# PWR.net
KiCad netlist of a schematic drawn in Altium Designer
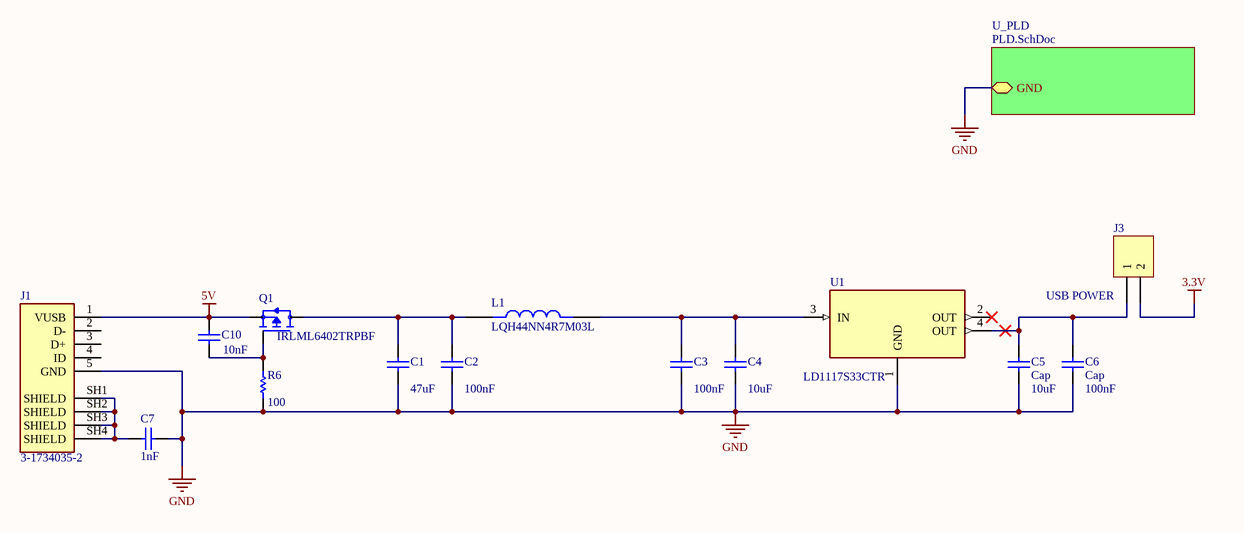
[diagram p0: PWR.SchDoc]

(export (version "E")
  (design (tool "Eeschema 10.0.6"))
  (components
    (comp (ref "C1")
      (value "47uF")
      (footprint "WCAP-CSGP_885012209019")
      (description "Capacitor")
      (fields (field (name "Comment") "Cap") (field (name "PUBLISHER") "Altium Limited"))
      (libsource (lib "Miscellaneous Devices") (part "Cap"))
    )
    (comp (ref "C2")
      (value "100nF")
      (footprint "WCAP-CSST_885382207009")
      (description "Capacitor")
      (fields (field (name "Comment") "Cap") (field (name "PUBLISHER") "Altium Limited"))
      (libsource (lib "Miscellaneous Devices") (part "Cap"))
    )
    (comp (ref "C3")
      (value "100nF")
      (footprint "WCAP-CSST_885382207009")
      (description "Capacitor")
      (fields (field (name "Comment") "Cap") (field (name "PUBLISHER") "Altium Limited"))
      (libsource (lib "Miscellaneous Devices") (part "Cap"))
    )
    (comp (ref "C4")
      (value "10uF")
      (footprint "WCAP-CSST_885382207009")
      (description "Capacitor")
      (fields (field (name "Comment") "Cap") (field (name "PUBLISHER") "Altium Limited"))
      (libsource (lib "Miscellaneous Devices") (part "Cap"))
    )
    (comp (ref "C5")
      (value "Cap")
      (footprint "WCAP-CSST_885382207009")
      (description "Capacitor")
      (fields (field (name "ALTIUM_VALUE") "10uF") (field (name "PUBLISHER") "Altium Limited"))
      (libsource (lib "Miscellaneous Devices") (part "Cap"))
    )
    (comp (ref "C6")
      (value "Cap")
      (footprint "WCAP-CSST_885382207009")
      (description "Capacitor")
      (fields (field (name "ALTIUM_VALUE") "100nF") (field (name "PUBLISHER") "Altium Limited"))
      (libsource (lib "Miscellaneous Devices") (part "Cap"))
    )
    (comp (ref "C7")
      (value "1nF")
      (footprint "WCAP-CSST_885382207009")
      (description "Capacitor")
      (fields (field (name "Comment") "Cap") (field (name "PUBLISHER") "Altium Limited"))
      (libsource (lib "Miscellaneous Devices") (part "Cap"))
    )
    (comp (ref "C10")
      (value "10nF")
      (footprint "WCAP-CSST_885382207009")
      (description "Capacitor")
      (fields (field (name "Comment") "Cap") (field (name "PUBLISHER") "Altium Limited"))
      (libsource (lib "Miscellaneous Devices") (part "Cap"))
    )
    (comp (ref "J1")
      (value "3-1734035-2")
      (footprint "TE_3-1734035-2")
      (description "USB Connectors MINI USB, R/A, SMT, MATTE TIN, W/O MYLAR")
      (fields (field (name "MF") "TE Connectivity"))
      (libsource (lib "3-1734035-2") (part "3-1734035-2"))
    )
    (comp (ref "J3")
      (value "USB POWER")
      (footprint "HDR1X2")
      (description "Header, 2-Pin")
      (fields (field (name "PUBLISHER") "Altium Limited"))
      (libsource (lib "Miscellaneous Connectors") (part "Header 2"))
    )
    (comp (ref "L1")
      (value "LQH44NN4R7M03L")
      (footprint "IND_LQH44NN4R7M03L")
      (description "FIXED IND 22UH 950MA 170 MOHM")
      (libsource (lib "LQH44NN4R7M03L") (part "LQH44NN4R7M03L"))
    )
    (comp (ref "Q1")
      (value "IRLML6402TRPBF")
      (footprint "SOT95P237X112-3N")
      (fields (field (name "MF") "Infineon"))
      (libsource (lib "IRLML6402TRPBF") (part "IRLML6402TRPBF"))
    )
    (comp (ref "R6")
      (value "100")
      (footprint "WCAP-CSST_885382207009")
      (description "Resistor")
      (fields (field (name "Comment") "Res1") (field (name "PUBLISHER") "Altium Limited"))
      (libsource (lib "Miscellaneous Devices") (part "Res1"))
    )
    (comp (ref "U1")
      (value "LD1117S33CTR")
      (footprint "SOT223")
      (description "Linear Voltage Regulator IC Positive Fixed 1 Output 800mA SOT-223")
      (fields (field (name "MF") "STMicroelectronics"))
      (libsource (lib "LD1117S33CTR") (part "LD1117S33CTR"))
    )
  )
  (nets
    (net (code "1") (name "3.3V") (class "Default")
      (node (ref "J3") (pin "2") (pinfunction "2_2") (pintype "passive"))
    )
    (net (code "2") (name "5V") (class "Default")
      (node (ref "C10") (pin "2") (pinfunction "2_2") (pintype "passive"))
      (node (ref "J1") (pin "1") (pinfunction "VUSB_1") (pintype "passive"))
      (node (ref "Q1") (pin "2") (pinfunction "S_2") (pintype "passive"))
    )
    (net (code "3") (name "GND") (class "Default")
      (node (ref "C1") (pin "1") (pinfunction "1_1") (pintype "passive"))
      (node (ref "C2") (pin "1") (pinfunction "1_1") (pintype "passive"))
      (node (ref "C3") (pin "1") (pinfunction "1_1") (pintype "passive"))
      (node (ref "C4") (pin "1") (pinfunction "1_1") (pintype "passive"))
      (node (ref "C5") (pin "1") (pinfunction "1_1") (pintype "passive"))
      (node (ref "C6") (pin "1") (pinfunction "1_1") (pintype "passive"))
      (node (ref "C7") (pin "2") (pinfunction "2_2") (pintype "passive"))
      (node (ref "J1") (pin "5") (pinfunction "GND_5") (pintype "passive"))
      (node (ref "R6") (pin "1") (pinfunction "1_1") (pintype "passive"))
      (node (ref "U1") (pin "1") (pinfunction "GND_1") (pintype "passive"))
    )
    (net (code "4") (name "Net-(C5-Pad2)") (class "Default")
      (node (ref "C5") (pin "2") (pinfunction "2_2") (pintype "passive"))
      (node (ref "C6") (pin "2") (pinfunction "2_2") (pintype "passive"))
      (node (ref "J3") (pin "1") (pinfunction "1_1") (pintype "passive"))
      (node (ref "U1") (pin "4") (pinfunction "OUT_4") (pintype "output"))
    )
    (net (code "5") (name "Net-(C7-Pad1)") (class "Default")
      (node (ref "C7") (pin "1") (pinfunction "1_1") (pintype "passive"))
      (node (ref "J1") (pin "SH1") (pinfunction "SHIELD_SH1") (pintype "passive"))
      (node (ref "J1") (pin "SH2") (pinfunction "SHIELD_SH2") (pintype "passive"))
      (node (ref "J1") (pin "SH3") (pinfunction "SHIELD_SH3") (pintype "passive"))
      (node (ref "J1") (pin "SH4") (pinfunction "SHIELD_SH4") (pintype "passive"))
    )
    (net (code "6") (name "Net-(Q1-D)") (class "Default")
      (node (ref "C1") (pin "2") (pinfunction "2_2") (pintype "passive"))
      (node (ref "C2") (pin "2") (pinfunction "2_2") (pintype "passive"))
      (node (ref "L1") (pin "1") (pinfunction "1_1") (pintype "passive"))
      (node (ref "Q1") (pin "3") (pinfunction "D_3") (pintype "passive"))
    )
    (net (code "7") (name "Net-(Q1-G)") (class "Default")
      (node (ref "C10") (pin "1") (pinfunction "1_1") (pintype "passive"))
      (node (ref "Q1") (pin "1") (pinfunction "G_1") (pintype "passive"))
      (node (ref "R6") (pin "2") (pinfunction "2_2") (pintype "passive"))
    )
    (net (code "8") (name "Net-(U1-IN)") (class "Default")
      (node (ref "C3") (pin "2") (pinfunction "2_2") (pintype "passive"))
      (node (ref "C4") (pin "2") (pinfunction "2_2") (pintype "passive"))
      (node (ref "L1") (pin "2") (pinfunction "2_2") (pintype "passive"))
      (node (ref "U1") (pin "3") (pinfunction "IN_3") (pintype "input"))
    )
    (net (code "9") (name "unconnected-(J1-D+-Pad3)") (class "Default")
      (node (ref "J1") (pin "3") (pinfunction "D+_3") (pintype "passive"))
    )
    (net (code "10") (name "unconnected-(J1-D--Pad2)") (class "Default")
      (node (ref "J1") (pin "2") (pinfunction "D-_2") (pintype "passive"))
    )
    (net (code "11") (name "unconnected-(J1-ID-Pad4)") (class "Default")
      (node (ref "J1") (pin "4") (pinfunction "ID_4") (pintype "passive"))
    )
    (net (code "12") (name "unconnected-(U1-OUT-Pad2)") (class "Default")
      (node (ref "U1") (pin "2") (pinfunction "OUT_2") (pintype "output+no_connect"))
    )
  )
)
